# ballon.net
KiCad netlist of a schematic drawn in EAGLE
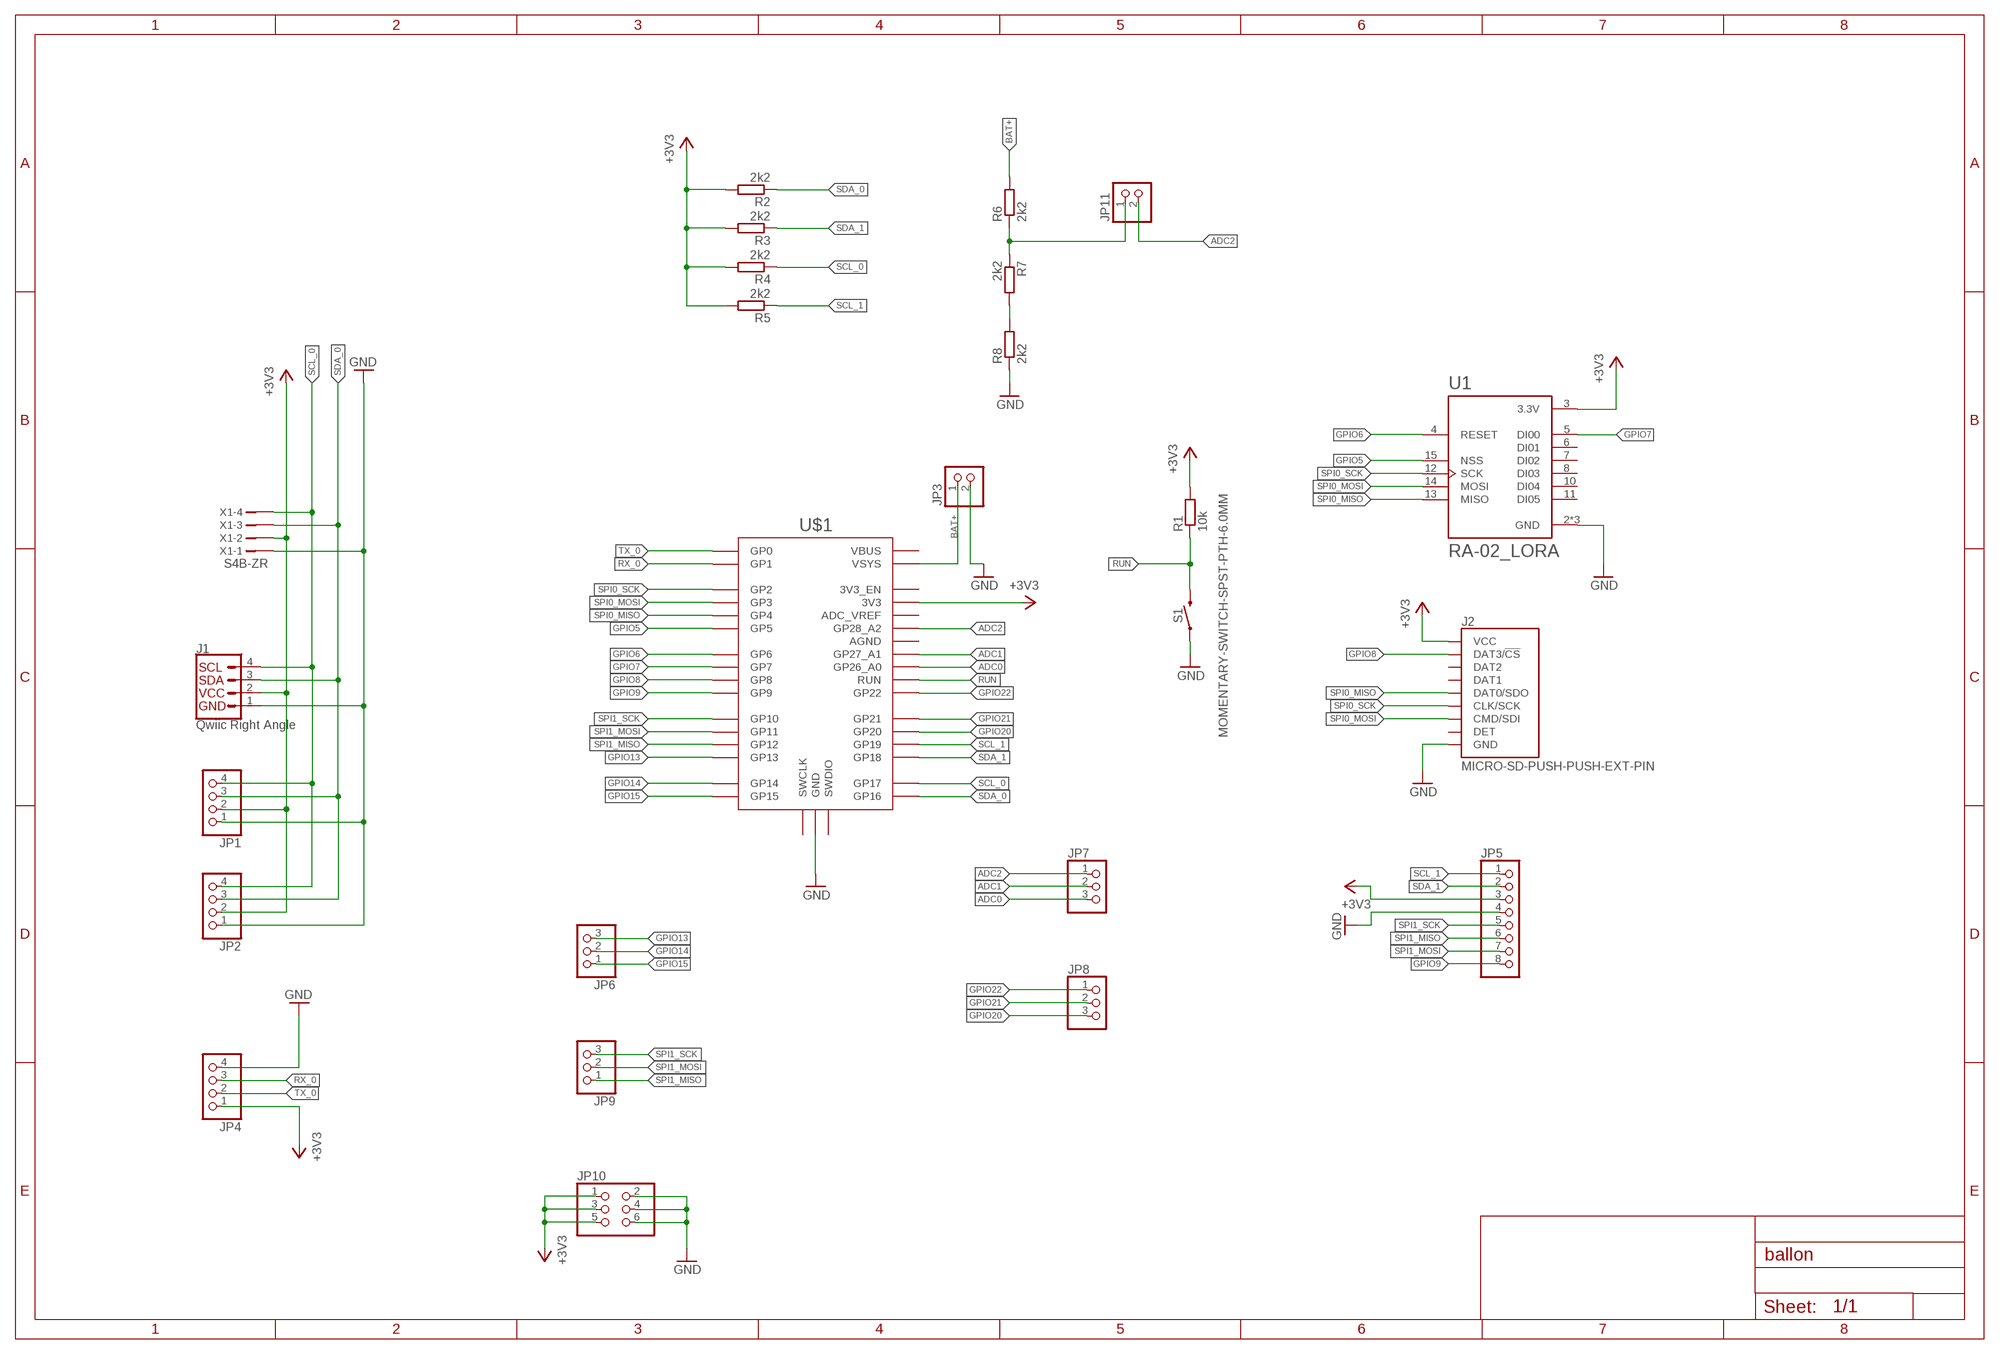
[diagram p0: schematic, sheet 1]

(export (version "E")
  (design (tool "Eeschema 10.0.6"))
  (components
    (comp (ref "J1")
      (value "Qwiic Right Angle")
      (footprint "eagle-import:JST04_1MM_RA")
      (libsource (lib "eagle-import") (part "I2C_STANDARDQWIIC"))
    )
    (comp (ref "J2")
      (value "MICRO-SD-PUSH-PUSH-EXT-PIN")
      (footprint "eagle-import:MICROSD-EXTERNALPIN")
      (libsource (lib "eagle-import") (part "MICRO-SD-PUSH-PUSH-EXT-PIN"))
    )
    (comp (ref "JP1")
      (value "PINHD-1X4")
      (footprint "eagle-import:1X04")
      (libsource (lib "eagle-import") (part "PINHD-1X4"))
    )
    (comp (ref "JP2")
      (value "PINHD-1X4")
      (footprint "eagle-import:1X04")
      (libsource (lib "eagle-import") (part "PINHD-1X4"))
    )
    (comp (ref "JP3")
      (value "PINHD-1X2")
      (footprint "eagle-import:1X02")
      (libsource (lib "eagle-import") (part "PINHD-1X2"))
    )
    (comp (ref "JP4")
      (value "PINHD-1X4")
      (footprint "eagle-import:1X04")
      (libsource (lib "eagle-import") (part "PINHD-1X4"))
    )
    (comp (ref "JP5")
      (value "PINHD-1X8")
      (footprint "eagle-import:1X08")
      (libsource (lib "eagle-import") (part "PINHD-1X8"))
    )
    (comp (ref "JP6")
      (value "PINHD-1X3")
      (footprint "eagle-import:1X03")
      (libsource (lib "eagle-import") (part "PINHD-1X3"))
    )
    (comp (ref "JP7")
      (value "PINHD-1X3")
      (footprint "eagle-import:1X03")
      (libsource (lib "eagle-import") (part "PINHD-1X3"))
    )
    (comp (ref "JP8")
      (value "PINHD-1X3")
      (footprint "eagle-import:1X03")
      (libsource (lib "eagle-import") (part "PINHD-1X3"))
    )
    (comp (ref "JP9")
      (value "PINHD-1X3")
      (footprint "eagle-import:1X03")
      (libsource (lib "eagle-import") (part "PINHD-1X3"))
    )
    (comp (ref "JP10")
      (value "PINHD-2X3")
      (footprint "eagle-import:2X03")
      (libsource (lib "eagle-import") (part "PINHD-2X3"))
    )
    (comp (ref "JP11")
      (value "PINHD-1X2")
      (footprint "eagle-import:1X02")
      (libsource (lib "eagle-import") (part "PINHD-1X2"))
    )
    (comp (ref "R1")
      (value "10k")
      (footprint "eagle-import:0204_7")
      (libsource (lib "eagle-import") (part "R-EU_0204/7"))
    )
    (comp (ref "R2")
      (value "2k2")
      (footprint "eagle-import:0204_7")
      (libsource (lib "eagle-import") (part "R-EU_0204/7"))
    )
    (comp (ref "R3")
      (value "2k2")
      (footprint "eagle-import:0204_7")
      (libsource (lib "eagle-import") (part "R-EU_0204/7"))
    )
    (comp (ref "R4")
      (value "2k2")
      (footprint "eagle-import:0204_7")
      (libsource (lib "eagle-import") (part "R-EU_0204/7"))
    )
    (comp (ref "R5")
      (value "2k2")
      (footprint "eagle-import:0204_7")
      (libsource (lib "eagle-import") (part "R-EU_0204/7"))
    )
    (comp (ref "R6")
      (value "2k2")
      (footprint "eagle-import:0204_7")
      (libsource (lib "eagle-import") (part "R-EU_0204/7"))
    )
    (comp (ref "R7")
      (value "2k2")
      (footprint "eagle-import:0204_7")
      (libsource (lib "eagle-import") (part "R-EU_0204/7"))
    )
    (comp (ref "R8")
      (value "2k2")
      (footprint "eagle-import:0204_7")
      (libsource (lib "eagle-import") (part "R-EU_0204/7"))
    )
    (comp (ref "S1")
      (value "MOMENTARY-SWITCH-SPST-PTH-6.0MM")
      (footprint "eagle-import:TACTILE_SWITCH_PTH_6.0MM")
      (libsource (lib "eagle-import") (part "MOMENTARY-SWITCH-SPST-PTH-6.0MM"))
    )
    (comp (ref "U$1")
      (value "RPI_PICO-SMD")
      (footprint "eagle-import:RPI_PICO")
      (libsource (lib "eagle-import") (part "RPI_PICO-SMD"))
    )
    (comp (ref "U1")
      (value "RA-02_LORA")
      (footprint "eagle-import:MODULE_RA-02_LORA")
      (fields (field (name "MF") "AI-Thinker") (field (name "MP") "Ra-02 LoRa"))
      (libsource (lib "eagle-import") (part "RA-02_LORA"))
    )
    (comp (ref "X1")
      (value "S4B-ZR")
      (footprint "eagle-import:S4B-ZR")
      (fields (field (name "MF") "FARNELL") (field (name "MPN") "S4B-ZR(LF)(SN)"))
      (libsource (lib "eagle-import") (part "?4B-ZRS"))
    )
  )
  (nets
    (net (code "1") (name "+3V3") (class "Default")
      (node (ref "J1") (pin "2") (pinfunction "2_2") (pintype "power_in"))
      (node (ref "J2") (pin "4") (pinfunction "VCC_4") (pintype "bidirectional"))
      (node (ref "JP1") (pin "2") (pinfunction "2_2") (pintype "passive"))
      (node (ref "JP10") (pin "1") (pinfunction "1_1") (pintype "passive"))
      (node (ref "JP10") (pin "3") (pinfunction "3_3") (pintype "passive"))
      (node (ref "JP10") (pin "5") (pinfunction "5_5") (pintype "passive"))
      (node (ref "JP2") (pin "2") (pinfunction "2_2") (pintype "passive"))
      (node (ref "JP4") (pin "1") (pinfunction "1_1") (pintype "passive"))
      (node (ref "JP5") (pin "3") (pinfunction "3_3") (pintype "passive"))
      (node (ref "R1") (pin "2") (pinfunction "2_2") (pintype "passive"))
      (node (ref "R2") (pin "2") (pinfunction "2_2") (pintype "passive"))
      (node (ref "R3") (pin "2") (pinfunction "2_2") (pintype "passive"))
      (node (ref "R4") (pin "2") (pinfunction "2_2") (pintype "passive"))
      (node (ref "R5") (pin "2") (pinfunction "2_2") (pintype "passive"))
      (node (ref "U$1") (pin "3V3") (pinfunction "3V3_3V3") (pintype "bidirectional"))
      (node (ref "U1") (pin "3") (pinfunction "3.3V_3") (pintype "power_in"))
      (node (ref "X1") (pin "2") (pinfunction "1_2") (pintype "passive"))
    )
    (net (code "2") (name "ADC0") (class "Default")
      (node (ref "JP7") (pin "3") (pinfunction "3_3") (pintype "passive"))
      (node (ref "U$1") (pin "GP26_A0") (pinfunction "GP26_A0_GP26_A0") (pintype "bidirectional"))
    )
    (net (code "3") (name "ADC1") (class "Default")
      (node (ref "JP7") (pin "2") (pinfunction "2_2") (pintype "passive"))
      (node (ref "U$1") (pin "GP27_A1") (pinfunction "GP27_A1_GP27_A1") (pintype "bidirectional"))
    )
    (net (code "4") (name "ADC2") (class "Default")
      (node (ref "JP11") (pin "2") (pinfunction "2_2") (pintype "passive"))
      (node (ref "JP7") (pin "1") (pinfunction "1_1") (pintype "passive"))
      (node (ref "U$1") (pin "GP28_A2") (pinfunction "GP28_A2_GP28_A2") (pintype "bidirectional"))
    )
    (net (code "5") (name "BAT+") (class "Default")
      (node (ref "JP3") (pin "1") (pinfunction "1_1") (pintype "passive"))
      (node (ref "R6") (pin "2") (pinfunction "2_2") (pintype "passive"))
      (node (ref "U$1") (pin "VSYS") (pinfunction "VSYS_VSYS") (pintype "bidirectional"))
    )
    (net (code "6") (name "GND") (class "Default")
      (node (ref "J1") (pin "1") (pinfunction "1_1") (pintype "power_in"))
      (node (ref "J2") (pin "10") (pinfunction "GND_10") (pintype "bidirectional"))
      (node (ref "J2") (pin "11") (pinfunction "GND_11") (pintype "bidirectional"))
      (node (ref "J2") (pin "12") (pinfunction "GND_12") (pintype "bidirectional"))
      (node (ref "J2") (pin "13") (pinfunction "GND_13") (pintype "bidirectional"))
      (node (ref "J2") (pin "6") (pinfunction "GND_6") (pintype "bidirectional"))
      (node (ref "JP1") (pin "1") (pinfunction "1_1") (pintype "passive"))
      (node (ref "JP10") (pin "2") (pinfunction "2_2") (pintype "passive"))
      (node (ref "JP10") (pin "4") (pinfunction "4_4") (pintype "passive"))
      (node (ref "JP10") (pin "6") (pinfunction "6_6") (pintype "passive"))
      (node (ref "JP2") (pin "1") (pinfunction "1_1") (pintype "passive"))
      (node (ref "JP3") (pin "2") (pinfunction "2_2") (pintype "passive"))
      (node (ref "JP4") (pin "4") (pinfunction "4_4") (pintype "passive"))
      (node (ref "JP5") (pin "4") (pinfunction "4_4") (pintype "passive"))
      (node (ref "R8") (pin "1") (pinfunction "1_1") (pintype "passive"))
      (node (ref "S1") (pin "1") (pinfunction "1_1") (pintype "passive"))
      (node (ref "U$1") (pin "GND@1") (pinfunction "GND_GND@1") (pintype "bidirectional"))
      (node (ref "U$1") (pin "GND@2") (pinfunction "GND_GND@2") (pintype "bidirectional"))
      (node (ref "U$1") (pin "GND@3") (pinfunction "GND_GND@3") (pintype "bidirectional"))
      (node (ref "U$1") (pin "GND@4") (pinfunction "GND_GND@4") (pintype "bidirectional"))
      (node (ref "U$1") (pin "GND@5") (pinfunction "GND_GND@5") (pintype "bidirectional"))
      (node (ref "U$1") (pin "GND@6") (pinfunction "GND_GND@6") (pintype "bidirectional"))
      (node (ref "U$1") (pin "GND@7") (pinfunction "GND_GND@7") (pintype "bidirectional"))
      (node (ref "U$1") (pin "GND@8") (pinfunction "GND_GND@8") (pintype "bidirectional"))
      (node (ref "U1") (pin "16") (pinfunction "GND_16") (pintype "power_in"))
      (node (ref "U1") (pin "2") (pinfunction "GND_2") (pintype "power_in"))
      (node (ref "U1") (pin "9") (pinfunction "GND_9") (pintype "power_in"))
      (node (ref "X1") (pin "1") (pinfunction "1_1") (pintype "passive"))
    )
    (net (code "7") (name "GPIO5") (class "Default")
      (node (ref "U$1") (pin "GP5") (pinfunction "GP5_GP5") (pintype "bidirectional"))
      (node (ref "U1") (pin "15") (pinfunction "NSS_15") (pintype "input"))
    )
    (net (code "8") (name "GPIO6") (class "Default")
      (node (ref "U$1") (pin "GP6") (pinfunction "GP6_GP6") (pintype "bidirectional"))
      (node (ref "U1") (pin "4") (pinfunction "RESET_4") (pintype "input"))
    )
    (net (code "9") (name "GPIO7") (class "Default")
      (node (ref "U$1") (pin "GP7") (pinfunction "GP7_GP7") (pintype "bidirectional"))
      (node (ref "U1") (pin "5") (pinfunction "DI00_5") (pintype "bidirectional"))
    )
    (net (code "10") (name "GPIO8") (class "Default")
      (node (ref "J2") (pin "2") (pinfunction "DAT3/~{CS}_2") (pintype "bidirectional"))
      (node (ref "U$1") (pin "GP8") (pinfunction "GP8_GP8") (pintype "bidirectional"))
    )
    (net (code "11") (name "GPIO9") (class "Default")
      (node (ref "JP5") (pin "8") (pinfunction "8_8") (pintype "passive"))
      (node (ref "U$1") (pin "GP9") (pinfunction "GP9_GP9") (pintype "bidirectional"))
    )
    (net (code "12") (name "GPIO13") (class "Default")
      (node (ref "JP6") (pin "3") (pinfunction "3_3") (pintype "passive"))
      (node (ref "U$1") (pin "GP13") (pinfunction "GP13_GP13") (pintype "bidirectional"))
    )
    (net (code "13") (name "GPIO14") (class "Default")
      (node (ref "JP6") (pin "2") (pinfunction "2_2") (pintype "passive"))
      (node (ref "U$1") (pin "GP14") (pinfunction "GP14_GP14") (pintype "bidirectional"))
    )
    (net (code "14") (name "GPIO15") (class "Default")
      (node (ref "JP6") (pin "1") (pinfunction "1_1") (pintype "passive"))
      (node (ref "U$1") (pin "GP15") (pinfunction "GP15_GP15") (pintype "bidirectional"))
    )
    (net (code "15") (name "GPIO20") (class "Default")
      (node (ref "JP8") (pin "3") (pinfunction "3_3") (pintype "passive"))
      (node (ref "U$1") (pin "GP20") (pinfunction "GP20_GP20") (pintype "bidirectional"))
    )
    (net (code "16") (name "GPIO21") (class "Default")
      (node (ref "JP8") (pin "2") (pinfunction "2_2") (pintype "passive"))
      (node (ref "U$1") (pin "GP21") (pinfunction "GP21_GP21") (pintype "bidirectional"))
    )
    (net (code "17") (name "GPIO22") (class "Default")
      (node (ref "JP8") (pin "1") (pinfunction "1_1") (pintype "passive"))
      (node (ref "U$1") (pin "GP22") (pinfunction "GP22_GP22") (pintype "bidirectional"))
    )
    (net (code "18") (name "Net-(JP11-Pad1)") (class "Default")
      (node (ref "JP11") (pin "1") (pinfunction "1_1") (pintype "passive"))
      (node (ref "R6") (pin "1") (pinfunction "1_1") (pintype "passive"))
      (node (ref "R7") (pin "1") (pinfunction "1_1") (pintype "passive"))
    )
    (net (code "19") (name "Net-(R7-Pad2)") (class "Default")
      (node (ref "R7") (pin "2") (pinfunction "2_2") (pintype "passive"))
      (node (ref "R8") (pin "2") (pinfunction "2_2") (pintype "passive"))
    )
    (net (code "20") (name "RUN") (class "Default")
      (node (ref "R1") (pin "1") (pinfunction "1_1") (pintype "passive"))
      (node (ref "S1") (pin "3") (pinfunction "2_3") (pintype "passive"))
      (node (ref "U$1") (pin "RUN") (pinfunction "RUN_RUN") (pintype "bidirectional"))
    )
    (net (code "21") (name "RX_0") (class "Default")
      (node (ref "JP4") (pin "3") (pinfunction "3_3") (pintype "passive"))
      (node (ref "U$1") (pin "GP1") (pinfunction "GP1_GP1") (pintype "bidirectional"))
    )
    (net (code "22") (name "SCL_0") (class "Default")
      (node (ref "J1") (pin "4") (pinfunction "4_4") (pintype "passive"))
      (node (ref "JP1") (pin "4") (pinfunction "4_4") (pintype "passive"))
      (node (ref "JP2") (pin "4") (pinfunction "4_4") (pintype "passive"))
      (node (ref "R4") (pin "1") (pinfunction "1_1") (pintype "passive"))
      (node (ref "U$1") (pin "GP17") (pinfunction "GP17_GP17") (pintype "bidirectional"))
      (node (ref "X1") (pin "4") (pinfunction "1_4") (pintype "passive"))
    )
    (net (code "23") (name "SCL_1") (class "Default")
      (node (ref "JP5") (pin "1") (pinfunction "1_1") (pintype "passive"))
      (node (ref "R5") (pin "1") (pinfunction "1_1") (pintype "passive"))
      (node (ref "U$1") (pin "GP19") (pinfunction "GP19_GP19") (pintype "bidirectional"))
    )
    (net (code "24") (name "SDA_0") (class "Default")
      (node (ref "J1") (pin "3") (pinfunction "3_3") (pintype "passive"))
      (node (ref "JP1") (pin "3") (pinfunction "3_3") (pintype "passive"))
      (node (ref "JP2") (pin "3") (pinfunction "3_3") (pintype "passive"))
      (node (ref "R2") (pin "1") (pinfunction "1_1") (pintype "passive"))
      (node (ref "U$1") (pin "GP16") (pinfunction "GP16_GP16") (pintype "bidirectional"))
      (node (ref "X1") (pin "3") (pinfunction "1_3") (pintype "passive"))
    )
    (net (code "25") (name "SDA_1") (class "Default")
      (node (ref "JP5") (pin "2") (pinfunction "2_2") (pintype "passive"))
      (node (ref "R3") (pin "1") (pinfunction "1_1") (pintype "passive"))
      (node (ref "U$1") (pin "GP18") (pinfunction "GP18_GP18") (pintype "bidirectional"))
    )
    (net (code "26") (name "SPI0_MISO") (class "Default")
      (node (ref "J2") (pin "7") (pinfunction "DAT0/SDO_7") (pintype "bidirectional"))
      (node (ref "U$1") (pin "GP4") (pinfunction "GP4_GP4") (pintype "bidirectional"))
      (node (ref "U1") (pin "13") (pinfunction "MISO_13") (pintype "output"))
    )
    (net (code "27") (name "SPI0_MOSI") (class "Default")
      (node (ref "J2") (pin "3") (pinfunction "CMD/SDI_3") (pintype "bidirectional"))
      (node (ref "U$1") (pin "GP3") (pinfunction "GP3_GP3") (pintype "bidirectional"))
      (node (ref "U1") (pin "14") (pinfunction "MOSI_14") (pintype "input"))
    )
    (net (code "28") (name "SPI0_SCK") (class "Default")
      (node (ref "J2") (pin "5") (pinfunction "CLK/SCK_5") (pintype "bidirectional"))
      (node (ref "U$1") (pin "GP2") (pinfunction "GP2_GP2") (pintype "bidirectional"))
      (node (ref "U1") (pin "12") (pinfunction "SCK_12") (pintype "input"))
    )
    (net (code "29") (name "SPI1_MISO") (class "Default")
      (node (ref "JP5") (pin "6") (pinfunction "6_6") (pintype "passive"))
      (node (ref "JP9") (pin "1") (pinfunction "1_1") (pintype "passive"))
      (node (ref "U$1") (pin "GP12") (pinfunction "GP12_GP12") (pintype "bidirectional"))
    )
    (net (code "30") (name "SPI1_MOSI") (class "Default")
      (node (ref "JP5") (pin "7") (pinfunction "7_7") (pintype "passive"))
      (node (ref "JP9") (pin "2") (pinfunction "2_2") (pintype "passive"))
      (node (ref "U$1") (pin "GP11") (pinfunction "GP11_GP11") (pintype "bidirectional"))
    )
    (net (code "31") (name "SPI1_SCK") (class "Default")
      (node (ref "JP5") (pin "5") (pinfunction "5_5") (pintype "passive"))
      (node (ref "JP9") (pin "3") (pinfunction "3_3") (pintype "passive"))
      (node (ref "U$1") (pin "GP10") (pinfunction "GP10_GP10") (pintype "bidirectional"))
    )
    (net (code "32") (name "TX_0") (class "Default")
      (node (ref "JP4") (pin "2") (pinfunction "2_2") (pintype "passive"))
      (node (ref "U$1") (pin "GP0") (pinfunction "GP0_GP0") (pintype "bidirectional"))
    )
    (net (code "33") (name "unconnected-(J2-DAT1-Pad8)") (class "Default")
      (node (ref "J2") (pin "8") (pinfunction "DAT1_8") (pintype "bidirectional"))
    )
    (net (code "34") (name "unconnected-(J2-DAT2-Pad1)") (class "Default")
      (node (ref "J2") (pin "1") (pinfunction "DAT2_1") (pintype "bidirectional"))
    )
    (net (code "35") (name "unconnected-(J2-DET-Pad9)") (class "Default")
      (node (ref "J2") (pin "9") (pinfunction "DET_9") (pintype "bidirectional"))
    )
    (net (code "36") (name "unconnected-(U$1-Pad3V3_EN)") (class "Default")
      (node (ref "U$1") (pin "3V3_EN") (pinfunction "3V3_EN_3V3_EN") (pintype "bidirectional"))
    )
    (net (code "37") (name "unconnected-(U$1-PadADC_VREF)") (class "Default")
      (node (ref "U$1") (pin "ADC_VREF") (pinfunction "ADC_VREF_ADC_VREF") (pintype "bidirectional"))
    )
    (net (code "38") (name "unconnected-(U$1-PadAGND)") (class "Default")
      (node (ref "U$1") (pin "AGND") (pinfunction "AGND_AGND") (pintype "bidirectional"))
    )
    (net (code "39") (name "unconnected-(U$1-PadSWCLK)") (class "Default")
      (node (ref "U$1") (pin "SWCLK") (pinfunction "SWCLK_SWCLK") (pintype "bidirectional"))
    )
    (net (code "40") (name "unconnected-(U$1-PadSWDIO)") (class "Default")
      (node (ref "U$1") (pin "SWDIO") (pinfunction "SWDIO_SWDIO") (pintype "bidirectional"))
    )
    (net (code "41") (name "unconnected-(U$1-PadVBUS)") (class "Default")
      (node (ref "U$1") (pin "VBUS") (pinfunction "VBUS_VBUS") (pintype "bidirectional"))
    )
    (net (code "42") (name "unconnected-(U1-DI01-Pad6)") (class "Default")
      (node (ref "U1") (pin "6") (pinfunction "DI01_6") (pintype "bidirectional"))
    )
    (net (code "43") (name "unconnected-(U1-DI02-Pad7)") (class "Default")
      (node (ref "U1") (pin "7") (pinfunction "DI02_7") (pintype "bidirectional"))
    )
    (net (code "44") (name "unconnected-(U1-DI03-Pad8)") (class "Default")
      (node (ref "U1") (pin "8") (pinfunction "DI03_8") (pintype "bidirectional"))
    )
    (net (code "45") (name "unconnected-(U1-DI04-Pad10)") (class "Default")
      (node (ref "U1") (pin "10") (pinfunction "DI04_10") (pintype "bidirectional"))
    )
    (net (code "46") (name "unconnected-(U1-DI05-Pad11)") (class "Default")
      (node (ref "U1") (pin "11") (pinfunction "DI05_11") (pintype "bidirectional"))
    )
  )
)
